# GNSS.net
KiCad netlist of a schematic drawn in Altium Designer
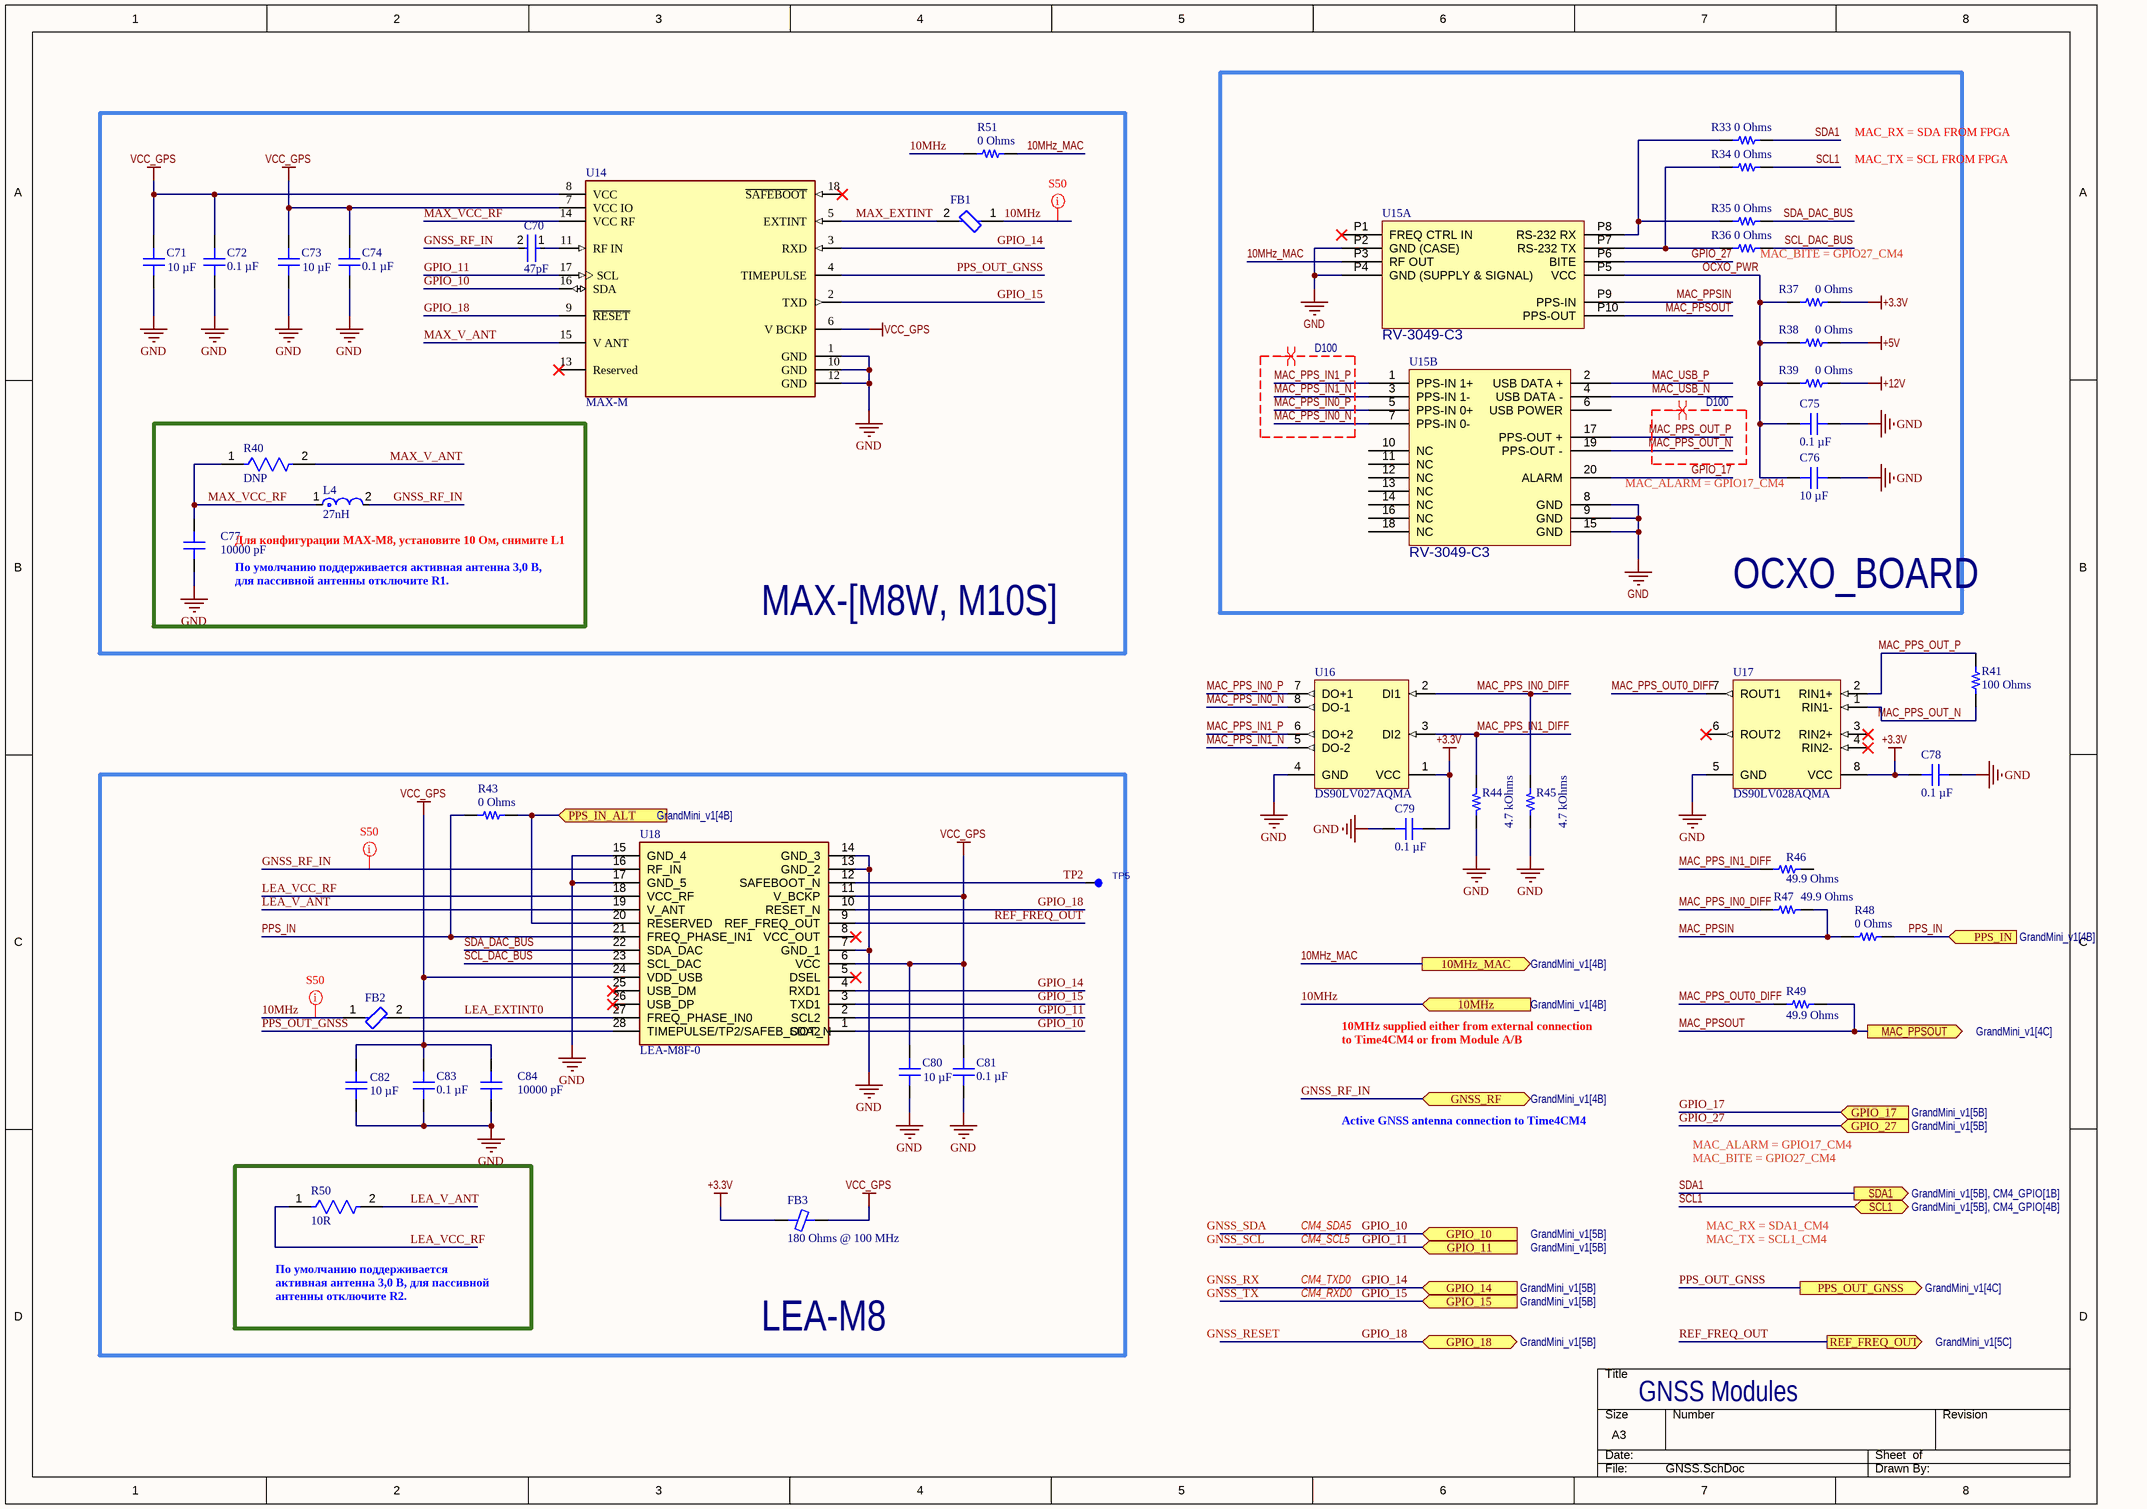
[diagram p0: GNSS.SchDoc]

(export (version "E")
  (design (tool "Eeschema 10.0.6"))
  (components
    (comp (ref "C70")
      (value "47pF")
      (footprint "FP-C0402-BB-MFG")
      (description "CAP CER 47PF 25V 5% NP0 0402")
      (fields
        (field (name "MANUFACTURER PART NUMBER") "C0402C470J3GACTU")
        (field (name "MANUFACTURER") "Kemet")
      )
      (libsource (lib "Altium Content Vault") (part "b4654b650e69147ec39a6b967a45e02"))
    )
    (comp (ref "C71")
      (value "10 µF")
      (footprint "CAP 0805_2012")
      (description "CAP CER 10UF 25V X5R 0805")
      (fields
        (field (name "TOLERANCE") "±10%")
        (field (name "CAPACITANCE") "10 µF")
        (field (name "PART NUMBER") "CC0805KKX5R8BB106")
      )
      (libsource (lib "Celestial Altium Library - altium_library") (part "Capacitor"))
    )
    (comp (ref "C72")
      (value "0.1 µF")
      (footprint "CAP 0603_1608")
      (description "CAP CER 0.1UF 50V X7R 0603")
      (fields (field (name "MANUFACTURER") "Yageo") (field (name "TOLERANCE") "±10%"))
      (libsource (lib "Celestial Altium Library - altium_library") (part "Capacitor"))
    )
    (comp (ref "C73")
      (value "~")
      (footprint "CAP 0805_2012")
      (description "CAP CER 10UF 25V X5R 0805")
      (fields
        (field (name "TOLERANCE") "±10%")
        (field (name "CAPACITANCE") "10 µF")
        (field (name "PART NUMBER") "CC0805KKX5R8BB106")
      )
      (libsource (lib "Celestial Altium Library - altium_library") (part "Capacitor"))
    )
    (comp (ref "C74")
      (value "0.1 µF")
      (footprint "CAP 0603_1608")
      (description "CAP CER 0.1UF 50V X7R 0603")
      (fields (field (name "MANUFACTURER") "Yageo") (field (name "TOLERANCE") "±10%"))
      (libsource (lib "Celestial Altium Library - altium_library") (part "Capacitor"))
    )
    (comp (ref "C75")
      (value "0.1 µF")
      (footprint "CAP 0603_1608")
      (description "CAP CER 0.1UF 50V X7R 0603")
      (fields (field (name "MANUFACTURER") "Yageo") (field (name "PART NUMBER") "CC0603KRX7R9BB104"))
      (libsource (lib "Celestial Altium Library - altium_library") (part "Capacitor"))
    )
    (comp (ref "C76")
      (value "10 µF")
      (footprint "CAP 0805_2012")
      (description "CAP CER 10UF 25V X5R 0805")
      (fields
        (field (name "TOLERANCE") "±10%")
        (field (name "CAPACITANCE") "10 µF")
        (field (name "PART NUMBER") "CC0805KKX5R8BB106")
      )
      (libsource (lib "Celestial Altium Library - altium_library") (part "Capacitor"))
    )
    (comp (ref "C77")
      (value "10000 pF")
      (footprint "CAP 0603_1608")
      (description "CAP CER 10000PF 50V X7R 0603")
      (fields (field (name "MANUFACTURER") "Yageo") (field (name "PART NUMBER") "CC0603KRX7R9BB103"))
      (libsource (lib "Celestial Altium Library - altium_library") (part "Capacitor"))
    )
    (comp (ref "C78")
      (value "0.1 µF")
      (footprint "CAP 0603_1608")
      (description "CAP CER 0.1UF 50V X7R 0603")
      (fields (field (name "MANUFACTURER") "Yageo") (field (name "PART NUMBER") "CC0603KRX7R9BB104"))
      (libsource (lib "Celestial Altium Library - altium_library") (part "Capacitor"))
    )
    (comp (ref "C79")
      (value "0.1 µF")
      (footprint "CAP 0603_1608")
      (description "CAP CER 0.1UF 50V X7R 0603")
      (fields (field (name "MANUFACTURER") "Yageo") (field (name "PART NUMBER") "CC0603KRX7R9BB104"))
      (libsource (lib "Celestial Altium Library - altium_library") (part "Capacitor"))
    )
    (comp (ref "C80")
      (value "10 µF")
      (footprint "CAP 0805_2012")
      (description "CAP CER 10UF 25V X5R 0805")
      (fields
        (field (name "TOLERANCE") "±10%")
        (field (name "CAPACITANCE") "10 µF")
        (field (name "PART NUMBER") "CC0805KKX5R8BB106")
      )
      (libsource (lib "Celestial Altium Library - altium_library") (part "Capacitor"))
    )
    (comp (ref "C81")
      (value "0.1 µF")
      (footprint "CAP 0603_1608")
      (description "CAP CER 0.1UF 50V X7R 0603")
      (fields (field (name "MANUFACTURER") "Yageo") (field (name "TOLERANCE") "±10%"))
      (libsource (lib "Celestial Altium Library - altium_library") (part "Capacitor"))
    )
    (comp (ref "C82")
      (value "10 µF")
      (footprint "CAP 0805_2012")
      (description "CAP CER 10UF 25V X5R 0805")
      (fields
        (field (name "TOLERANCE") "±10%")
        (field (name "CAPACITANCE") "10 µF")
        (field (name "PART NUMBER") "CC0805KKX5R8BB106")
      )
      (libsource (lib "Celestial Altium Library - altium_library") (part "Capacitor"))
    )
    (comp (ref "C83")
      (value "0.1 µF")
      (footprint "CAP 0603_1608")
      (description "CAP CER 0.1UF 50V X7R 0603")
      (fields (field (name "MANUFACTURER") "Yageo") (field (name "TOLERANCE") "±10%"))
      (libsource (lib "Celestial Altium Library - altium_library") (part "Capacitor"))
    )
    (comp (ref "C84")
      (value "10000 pF")
      (footprint "CAP 0603_1608")
      (description "CAP CER 10000PF 50V X7R 0603")
      (fields (field (name "MANUFACTURER") "Yageo") (field (name "PART NUMBER") "CC0603KRX7R9BB103"))
      (libsource (lib "Celestial Altium Library - altium_library") (part "Capacitor"))
    )
    (comp (ref "FB1")
      (value "BLM18HG102SH1D")
      (footprint "FP-BLM18-0_15-t0_8-IPC_C")
      (description "Chip Ferrite Bead, 0603, 1000Ω @ 100MHz, 1.6Ω, 25%, 100mA")
      (fields (field (name "TOLERANCE") "25%"))
      (libsource (lib "Altium Content Vault") (part "5f30dd21d616792df468990f7003faa"))
    )
    (comp (ref "FB2")
      (value "BLM18HG102SH1D")
      (footprint "FP-BLM18-0_15-t0_8-IPC_C")
      (description "Chip Ferrite Bead, 0603, 1000Ω @ 100MHz, 1.6Ω, 25%, 100mA")
      (fields (field (name "TOLERANCE") "25%"))
      (libsource (lib "Altium Content Vault") (part "5f30dd21d616792df468990f7003faa"))
    )
    (comp (ref "FB3")
      (value "180 Ohms @ 100 MHz")
      (footprint "FER 0603_1608")
      (description "FERRITE BEAD 180 OHM 0603 1LN")
      (fields
        (field (name "PART NUMBER") "BLM18PG181SN1D")
        (field (name "MANUFACTURER") "Murata Electronics")
      )
      (libsource (lib "Celestial Altium Library - altium_library") (part "Ferrite Chip"))
    )
    (comp (ref "L4")
      (value "27nH")
      (footprint "FP-LQG15HH_02-IPC_C")
      (description "Multilayer type RF Inductor 27nH ±5% 0.46Ω 350mA 0402")
      (fields (field (name "TOLERANCE") "5%"))
      (libsource (lib "Altium Content Vault") (part "4cc4b267dca4c8e51f7102f422741d8"))
    )
    (comp (ref "R33")
      (value "0 Ohms")
      (footprint "YAGEO RES 0805_2012")
      (description "RES 0 OHM JUMPER 1/8W 0805")
      (fields (field (name "PART NUMBER") "RC0805FR-070RL") (field (name "MANUFACTURER") "Yageo"))
      (libsource (lib "Celestial Altium Library - altium_library") (part "Resistor"))
    )
    (comp (ref "R34")
      (value "0 Ohms")
      (footprint "YAGEO RES 0805_2012")
      (description "RES 0 OHM JUMPER 1/8W 0805")
      (fields (field (name "PART NUMBER") "RC0805FR-070RL") (field (name "MANUFACTURER") "Yageo"))
      (libsource (lib "Celestial Altium Library - altium_library") (part "Resistor"))
    )
    (comp (ref "R35")
      (value "0 Ohms")
      (footprint "YAGEO RES 0805_2012")
      (description "RES 0 OHM JUMPER 1/8W 0805")
      (fields (field (name "PART NUMBER") "RC0805FR-070RL") (field (name "MANUFACTURER") "Yageo"))
      (libsource (lib "Celestial Altium Library - altium_library") (part "Resistor"))
    )
    (comp (ref "R36")
      (value "0 Ohms")
      (footprint "YAGEO RES 0805_2012")
      (description "RES 0 OHM JUMPER 1/8W 0805")
      (fields (field (name "PART NUMBER") "RC0805FR-070RL") (field (name "MANUFACTURER") "Yageo"))
      (libsource (lib "Celestial Altium Library - altium_library") (part "Resistor"))
    )
    (comp (ref "R37")
      (value "0 Ohms")
      (footprint "YAGEO RES 0805_2012")
      (description "RES 0 OHM JUMPER 1/8W 0805")
      (fields (field (name "PART NUMBER") "RC0805FR-070RL") (field (name "MANUFACTURER") "Yageo"))
      (libsource (lib "Celestial Altium Library - altium_library") (part "Resistor"))
    )
    (comp (ref "R38")
      (value "0 Ohms")
      (footprint "YAGEO RES 0805_2012")
      (description "RES 0 OHM JUMPER 1/8W 0805")
      (fields (field (name "PART NUMBER") "RC0805FR-070RL") (field (name "MANUFACTURER") "Yageo"))
      (libsource (lib "Celestial Altium Library - altium_library") (part "Resistor"))
    )
    (comp (ref "R39")
      (value "0 Ohms")
      (footprint "YAGEO RES 0805_2012")
      (description "RES 0 OHM JUMPER 1/8W 0805")
      (fields (field (name "PART NUMBER") "RC0805FR-070RL") (field (name "MANUFACTURER") "Yageo"))
      (libsource (lib "Celestial Altium Library - altium_library") (part "Resistor"))
    )
    (comp (ref "R40")
      (value "DNP")
      (footprint "FP-ERJ3EK-MFG")
      (description "RES SMD 10 OHM 1% 1/10W 0603")
      (fields
        (field (name "OCTOPART") "https://octopart.com/erj-3ekf10r0v-panasonic-55403649")
        (field (name "MANUFACTURER PART NUMBER") "ERJ-3EKF10R0V")
      )
      (libsource (lib "Altium Content Vault") (part "1029c3af85768c4190bb7ad29bc67b5"))
    )
    (comp (ref "R41")
      (value "100 Ohms")
      (footprint "YAGEO RES 0603_1608")
      (description "RES 100 OHM 1% 1/10W 0603")
      (fields (field (name "PART NUMBER") "RC0603FR-07100RL") (field (name "MANUFACTURER") "Yageo"))
      (libsource (lib "Celestial Altium Library - altium_library") (part "Resistor"))
    )
    (comp (ref "R43")
      (value "0 Ohms")
      (footprint "YAGEO RES 0805_2012")
      (description "RES 0 OHM JUMPER 1/8W 0805")
      (fields (field (name "TOLERANCE") "Jumper") (field (name "MANUFACTURER") "Yageo"))
      (libsource (lib "Celestial Altium Library - altium_library") (part "Resistor"))
    )
    (comp (ref "R44")
      (value "4.7 kOhms")
      (footprint "YAGEO RES 0402_1005")
      (description "RES 4.7K OHM 1% 1/16W 0402")
      (fields (field (name "MANUFACTURER") "Yageo") (field (name "TOLERANCE") "±1%"))
      (libsource (lib "Celestial Altium Library - altium_library") (part "Resistor"))
    )
    (comp (ref "R45")
      (value "4.7 kOhms")
      (footprint "YAGEO RES 0402_1005")
      (description "RES 4.7K OHM 1% 1/16W 0402")
      (fields (field (name "MANUFACTURER") "Yageo") (field (name "TOLERANCE") "±1%"))
      (libsource (lib "Celestial Altium Library - altium_library") (part "Resistor"))
    )
    (comp (ref "R46")
      (value "49.9 Ohms")
      (footprint "YAGEO RES 0603_1608")
      (description "RES 49.9 OHM 1% 1/10W 0603")
      (fields (field (name "PART NUMBER") "RC0603FR-0749R9L") (field (name "MANUFACTURER") "Yageo"))
      (libsource (lib "Celestial Altium Library - altium_library") (part "Resistor"))
    )
    (comp (ref "R47")
      (value "49.9 Ohms")
      (footprint "YAGEO RES 0603_1608")
      (description "RES 49.9 OHM 1% 1/10W 0603")
      (fields (field (name "PART NUMBER") "RC0603FR-0749R9L") (field (name "MANUFACTURER") "Yageo"))
      (libsource (lib "Celestial Altium Library - altium_library") (part "Resistor"))
    )
    (comp (ref "R48")
      (value "0 Ohms")
      (footprint "YAGEO RES 0805_2012")
      (description "RES 0 OHM JUMPER 1/8W 0805")
      (fields (field (name "TOLERANCE") "Jumper") (field (name "MANUFACTURER") "Yageo"))
      (libsource (lib "Celestial Altium Library - altium_library") (part "Resistor"))
    )
    (comp (ref "R49")
      (value "49.9 Ohms")
      (footprint "YAGEO RES 0603_1608")
      (description "RES 49.9 OHM 1% 1/10W 0603")
      (fields (field (name "PART NUMBER") "RC0603FR-0749R9L") (field (name "MANUFACTURER") "Yageo"))
      (libsource (lib "Celestial Altium Library - altium_library") (part "Resistor"))
    )
    (comp (ref "R50")
      (value "10R")
      (footprint "FP-ERJ3EK-MFG")
      (description "RES SMD 10 OHM 1% 1/10W 0603")
      (fields
        (field (name "OCTOPART") "https://octopart.com/erj-3ekf10r0v-panasonic-55403649")
        (field (name "MANUFACTURER PART NUMBER") "ERJ-3EKF10R0V")
      )
      (libsource (lib "Altium Content Vault") (part "1029c3af85768c4190bb7ad29bc67b5"))
    )
    (comp (ref "R51")
      (value "0 Ohms")
      (footprint "YAGEO RES 0805_2012")
      (description "RES 0 OHM JUMPER 1/8W 0805")
      (fields (field (name "TOLERANCE") "Jumper") (field (name "MANUFACTURER") "Yageo"))
      (libsource (lib "Celestial Altium Library - altium_library") (part "Resistor"))
    )
    (comp (ref "TP5")
      (value "PAD_TEST")
      (footprint "Samacsys:PAD_TEST")
      (description "Test Point")
      (fields (field (name "TOLERANCE") "{Tolerance}") (field (name "MANUFACTURER") "{Manufacturer}"))
      (libsource (lib "SamacSys") (part "PAD_TEST"))
    )
    (comp (ref "U14")
      (value "MAX-M")
      (footprint "FP-MAX-M8W-0-MFG")
      (description "RF RCVR GNSS/GPS 1.575GHZ 18LCC")
      (libsource (lib "Altium Content Vault") (part "36e94f557bbf38d877319147cff7e99"))
    )
    (comp (ref "U15")
      (value "RV-3049-C3")
      (footprint "OCXO_CARD")
      (description "MOD, MAC, MAC-SA5X, ATOMIC CLOCK")
      (fields (field (name "MFG PART NUM") "MAC-SA5X") (field (name "VELENTIUM PART NUM") "<V PART NUM>"))
      (libsource (lib "SHIWA_lib") (part "MAC-SA5X"))
    )
    (comp (ref "U16")
      (value "DS90LV027AQMA")
      (footprint "M08A_N")
      (description "Automotive LVDS Dual Differential Driver, 8-pin Narrow SOIC")
      (fields (field (name "MANUFACTURER") "National Semiconductor"))
      (libsource (lib "Altium Content Vault") (part "IN-LNDRV-DS90LV027AHM"))
    )
    (comp (ref "U17")
      (value "DS90LV028AQMA")
      (footprint "M08A_L")
      (description "Automotive LVDS Dual Differential Line Receiver, 8-pin Narrow SOIC")
      (fields (field (name "MANUFACTURER") "National Semiconductor"))
      (libsource (lib "Altium Content Vault") (part "IN-LNRX-DS90LV028AHM"))
    )
    (comp (ref "U18")
      (value "LEA-M8F-0")
      (footprint "SamacSys:LEAM8F0")
      (description "Integrated Circuit")
      (fields (field (name "MOUSER PART NUMBER") "377-LEA-M8F-0"))
      (libsource (lib "SamacSys") (part "LEA-M8F-0"))
    )
  )
  (nets
    (net (code "1") (name "+3.3V") (class "Default")
      (node (ref "C78") (pin "1") (pinfunction "1_1") (pintype "passive"))
      (node (ref "C79") (pin "2") (pinfunction "2_2") (pintype "passive"))
      (node (ref "FB3") (pin "1") (pinfunction "1_1") (pintype "passive"))
      (node (ref "R37") (pin "1") (pinfunction "1_1") (pintype "passive"))
      (node (ref "U16") (pin "1") (pinfunction "VCC_1") (pintype "power_in"))
      (node (ref "U17") (pin "8") (pinfunction "VCC_8") (pintype "power_in"))
    )
    (net (code "2") (name "+5V") (class "Default")
      (node (ref "R38") (pin "1") (pinfunction "1_1") (pintype "passive"))
    )
    (net (code "3") (name "+12V") (class "Default")
      (node (ref "R39") (pin "1") (pinfunction "1_1") (pintype "passive"))
    )
    (net (code "4") (name "/10MHz") (class "Default")
      (node (ref "FB1") (pin "1") (pinfunction "1_1") (pintype "passive"))
      (node (ref "FB2") (pin "1") (pinfunction "1_1") (pintype "passive"))
      (node (ref "R51") (pin "1") (pinfunction "1_1") (pintype "passive"))
    )
    (net (code "5") (name "/10MHz_MAC") (class "Default")
      (node (ref "R51") (pin "2") (pinfunction "2_2") (pintype "passive"))
      (node (ref "U15") (pin "P3") (pinfunction "RF_OUT_P3") (pintype "passive"))
    )
    (net (code "6") (name "/GNSS_RF_IN") (class "Default")
      (node (ref "C70") (pin "2") (pinfunction "2_2") (pintype "passive"))
      (node (ref "L4") (pin "2") (pinfunction "2_2") (pintype "passive"))
      (node (ref "U18") (pin "16") (pinfunction "RF_IN_16") (pintype "passive"))
    )
    (net (code "7") (name "/GPIO_10") (class "Default")
      (node (ref "U14") (pin "16") (pinfunction "SDA_16") (pintype "bidirectional"))
      (node (ref "U18") (pin "1") (pinfunction "SDA2_1") (pintype "passive"))
    )
    (net (code "8") (name "/GPIO_11") (class "Default")
      (node (ref "U14") (pin "17") (pinfunction "SCL_17") (pintype "input"))
      (node (ref "U18") (pin "2") (pinfunction "SCL2_2") (pintype "passive"))
    )
    (net (code "9") (name "/GPIO_14") (class "Default")
      (node (ref "U14") (pin "3") (pinfunction "RXD_3") (pintype "input"))
      (node (ref "U18") (pin "4") (pinfunction "RXD1_4") (pintype "passive"))
    )
    (net (code "10") (name "/GPIO_15") (class "Default")
      (node (ref "U14") (pin "2") (pinfunction "TXD_2") (pintype "output"))
      (node (ref "U18") (pin "3") (pinfunction "TXD1_3") (pintype "passive"))
    )
    (net (code "11") (name "/GPIO_17") (class "Default")
      (node (ref "U15") (pin "20") (pinfunction "ALARM_20") (pintype "passive"))
    )
    (net (code "12") (name "/GPIO_18") (class "Default")
      (node (ref "U14") (pin "9") (pinfunction "~{RESET}_9") (pintype "passive"))
      (node (ref "U18") (pin "10") (pinfunction "RESET_N_10") (pintype "passive"))
    )
    (net (code "13") (name "/GPIO_27") (class "Default")
      (node (ref "U15") (pin "P6") (pinfunction "BITE_P6") (pintype "passive"))
    )
    (net (code "14") (name "/LEA_EXTINT0") (class "Default")
      (node (ref "FB2") (pin "2") (pinfunction "2_2") (pintype "passive"))
      (node (ref "U18") (pin "27") (pinfunction "FREQ_PHASE_IN0_27") (pintype "passive"))
    )
    (net (code "15") (name "/LEA_VCC_RF") (class "Default")
      (node (ref "R50") (pin "1") (pinfunction "1_1") (pintype "passive"))
      (node (ref "U18") (pin "18") (pinfunction "VCC_RF_18") (pintype "passive"))
    )
    (net (code "16") (name "/LEA_V_ANT") (class "Default")
      (node (ref "R50") (pin "2") (pinfunction "2_2") (pintype "passive"))
      (node (ref "U18") (pin "19") (pinfunction "V_ANT_19") (pintype "passive"))
    )
    (net (code "17") (name "/MAC_PPSIN") (class "Default")
      (node (ref "R47") (pin "2") (pinfunction "2_2") (pintype "passive"))
      (node (ref "R48") (pin "1") (pinfunction "1_1") (pintype "passive"))
      (node (ref "U15") (pin "P9") (pinfunction "PPS-IN_P9") (pintype "passive"))
    )
    (net (code "18") (name "/MAC_PPSOUT") (class "Default")
      (node (ref "R49") (pin "2") (pinfunction "2_2") (pintype "passive"))
      (node (ref "U15") (pin "P10") (pinfunction "PPS-OUT_P10") (pintype "passive"))
    )
    (net (code "19") (name "/MAC_PPS_IN0_DIFF") (class "Default")
      (node (ref "R45") (pin "2") (pinfunction "2_2") (pintype "passive"))
      (node (ref "R47") (pin "1") (pinfunction "1_1") (pintype "passive"))
      (node (ref "U16") (pin "2") (pinfunction "DI1_2") (pintype "input"))
    )
    (net (code "20") (name "/MAC_PPS_IN0_N") (class "Default")
      (node (ref "U15") (pin "7") (pinfunction "PPS-IN_0-_7") (pintype "passive"))
      (node (ref "U16") (pin "8") (pinfunction "DO-1_8") (pintype "output"))
    )
    (net (code "21") (name "/MAC_PPS_IN0_P") (class "Default")
      (node (ref "U15") (pin "5") (pinfunction "PPS-IN_0+_5") (pintype "passive"))
      (node (ref "U16") (pin "7") (pinfunction "DO+1_7") (pintype "output"))
    )
    (net (code "22") (name "/MAC_PPS_IN1_DIFF") (class "Default")
      (node (ref "R44") (pin "2") (pinfunction "2_2") (pintype "passive"))
      (node (ref "R46") (pin "1") (pinfunction "1_1") (pintype "passive"))
      (node (ref "U16") (pin "3") (pinfunction "DI2_3") (pintype "input"))
    )
    (net (code "23") (name "/MAC_PPS_IN1_N") (class "Default")
      (node (ref "U15") (pin "3") (pinfunction "PPS-IN_1-_3") (pintype "passive"))
      (node (ref "U16") (pin "5") (pinfunction "DO-2_5") (pintype "output"))
    )
    (net (code "24") (name "/MAC_PPS_IN1_P") (class "Default")
      (node (ref "U15") (pin "1") (pinfunction "PPS-IN_1+_1") (pintype "passive"))
      (node (ref "U16") (pin "6") (pinfunction "DO+2_6") (pintype "output"))
    )
    (net (code "25") (name "/MAC_PPS_OUT0_DIFF") (class "Default")
      (node (ref "R49") (pin "1") (pinfunction "1_1") (pintype "passive"))
      (node (ref "U17") (pin "7") (pinfunction "ROUT1_7") (pintype "output"))
    )
    (net (code "26") (name "/MAC_PPS_OUT_N") (class "Default")
      (node (ref "R41") (pin "1") (pinfunction "1_1") (pintype "passive"))
      (node (ref "U15") (pin "19") (pinfunction "PPS-OUT_-_19") (pintype "passive"))
      (node (ref "U17") (pin "1") (pinfunction "RIN1-_1") (pintype "input"))
    )
    (net (code "27") (name "/MAC_PPS_OUT_P") (class "Default")
      (node (ref "R41") (pin "2") (pinfunction "2_2") (pintype "passive"))
      (node (ref "U15") (pin "17") (pinfunction "PPS-OUT_+_17") (pintype "passive"))
      (node (ref "U17") (pin "2") (pinfunction "RIN1+_2") (pintype "input"))
    )
    (net (code "28") (name "/MAC_USB_N") (class "Default")
      (node (ref "U15") (pin "4") (pinfunction "USB_DATA_-_4") (pintype "passive"))
    )
    (net (code "29") (name "/MAC_USB_P") (class "Default")
      (node (ref "U15") (pin "2") (pinfunction "USB_DATA_+_2") (pintype "passive"))
    )
    (net (code "30") (name "/MAX_EXTINT") (class "Default")
      (node (ref "FB1") (pin "2") (pinfunction "2_2") (pintype "passive"))
      (node (ref "U14") (pin "5") (pinfunction "EXTINT_5") (pintype "input"))
    )
    (net (code "31") (name "/MAX_VCC_RF") (class "Default")
      (node (ref "C77") (pin "2") (pinfunction "2_2") (pintype "passive"))
      (node (ref "L4") (pin "1") (pinfunction "1_1") (pintype "passive"))
      (node (ref "R40") (pin "1") (pinfunction "1_1") (pintype "passive"))
      (node (ref "U14") (pin "14") (pinfunction "VCC_RF_14") (pintype "power_in"))
    )
    (net (code "32") (name "/MAX_V_ANT") (class "Default")
      (node (ref "R40") (pin "2") (pinfunction "2_2") (pintype "passive"))
      (node (ref "U14") (pin "15") (pinfunction "V_ANT_15") (pintype "power_in"))
    )
    (net (code "33") (name "/OCXO_PWR") (class "Default")
      (node (ref "C75") (pin "1") (pinfunction "1_1") (pintype "passive"))
      (node (ref "C76") (pin "2") (pinfunction "2_2") (pintype "passive"))
      (node (ref "R37") (pin "2") (pinfunction "2_2") (pintype "passive"))
      (node (ref "R38") (pin "2") (pinfunction "2_2") (pintype "passive"))
      (node (ref "R39") (pin "2") (pinfunction "2_2") (pintype "passive"))
      (node (ref "U15") (pin "P5") (pinfunction "VCC_P5") (pintype "passive"))
    )
    (net (code "34") (name "/PPS_IN") (class "Default")
      (node (ref "R43") (pin "1") (pinfunction "1_1") (pintype "passive"))
      (node (ref "R48") (pin "2") (pinfunction "2_2") (pintype "passive"))
      (node (ref "U18") (pin "21") (pinfunction "FREQ_PHASE_IN1_21") (pintype "passive"))
    )
    (net (code "35") (name "/PPS_IN_ALT") (class "Default")
      (node (ref "R43") (pin "2") (pinfunction "2_2") (pintype "passive"))
      (node (ref "U18") (pin "20") (pinfunction "RESERVED_20") (pintype "passive"))
    )
    (net (code "36") (name "/PPS_OUT_GNSS") (class "Default")
      (node (ref "U14") (pin "4") (pinfunction "TIMEPULSE_4") (pintype "passive"))
      (node (ref "U18") (pin "28") (pinfunction "TIMEPULSE/TP2/SAFEB_OOT_N_28") (pintype "passive"))
    )
    (net (code "37") (name "/REF_FREQ_OUT") (class "Default")
      (node (ref "U18") (pin "9") (pinfunction "REF_FREQ_OUT_9") (pintype "passive"))
    )
    (net (code "38") (name "/SCL1") (class "Default")
      (node (ref "R34") (pin "1") (pinfunction "1_1") (pintype "passive"))
    )
    (net (code "39") (name "/SCL_DAC_BUS") (class "Default")
      (node (ref "R36") (pin "1") (pinfunction "1_1") (pintype "passive"))
      (node (ref "U18") (pin "23") (pinfunction "SCL_DAC_23") (pintype "passive"))
    )
    (net (code "40") (name "/SDA1") (class "Default")
      (node (ref "R33") (pin "1") (pinfunction "1_1") (pintype "passive"))
    )
    (net (code "41") (name "/SDA_DAC_BUS") (class "Default")
      (node (ref "R35") (pin "1") (pinfunction "1_1") (pintype "passive"))
      (node (ref "U18") (pin "22") (pinfunction "SDA_DAC_22") (pintype "passive"))
    )
    (net (code "42") (name "/TP2") (class "Default")
      (node (ref "TP5") (pin "1") (pinfunction "1_1") (pintype "passive"))
      (node (ref "U18") (pin "12") (pinfunction "SAFEBOOT_N_12") (pintype "passive"))
    )
    (net (code "43") (name "GND") (class "Default")
      (node (ref "C71") (pin "1") (pinfunction "1_1") (pintype "passive"))
      (node (ref "C72") (pin "1") (pinfunction "1_1") (pintype "passive"))
      (node (ref "C73") (pin "1") (pinfunction "1_1") (pintype "passive"))
      (node (ref "C74") (pin "1") (pinfunction "1_1") (pintype "passive"))
      (node (ref "C75") (pin "2") (pinfunction "2_2") (pintype "passive"))
      (node (ref "C76") (pin "1") (pinfunction "1_1") (pintype "passive"))
      (node (ref "C77") (pin "1") (pinfunction "1_1") (pintype "passive"))
      (node (ref "C78") (pin "2") (pinfunction "2_2") (pintype "passive"))
      (node (ref "C79") (pin "1") (pinfunction "1_1") (pintype "passive"))
      (node (ref "C80") (pin "1") (pinfunction "1_1") (pintype "passive"))
      (node (ref "C81") (pin "1") (pinfunction "1_1") (pintype "passive"))
      (node (ref "C82") (pin "1") (pinfunction "1_1") (pintype "passive"))
      (node (ref "C83") (pin "1") (pinfunction "1_1") (pintype "passive"))
      (node (ref "C84") (pin "1") (pinfunction "1_1") (pintype "passive"))
      (node (ref "R44") (pin "1") (pinfunction "1_1") (pintype "passive"))
      (node (ref "R45") (pin "1") (pinfunction "1_1") (pintype "passive"))
      (node (ref "U14") (pin "1") (pinfunction "GND_1") (pintype "power_in"))
      (node (ref "U14") (pin "10") (pinfunction "GND_10") (pintype "power_in"))
      (node (ref "U14") (pin "12") (pinfunction "GND_12") (pintype "power_in"))
      (node (ref "U15") (pin "15") (pinfunction "GND_15") (pintype "passive"))
      (node (ref "U15") (pin "8") (pinfunction "GND_8") (pintype "passive"))
      (node (ref "U15") (pin "9") (pinfunction "GND_9") (pintype "passive"))
      (node (ref "U15") (pin "P2") (pinfunction "GND_(CASE)_P2") (pintype "passive"))
      (node (ref "U15") (pin "P4") (pinfunction "GND_(SUPPLY_&_SIGNAL)_P4") (pintype "passive"))
      (node (ref "U16") (pin "4") (pinfunction "GND_4") (pintype "power_in"))
      (node (ref "U17") (pin "5") (pinfunction "GND_5") (pintype "power_in"))
      (node (ref "U18") (pin "13") (pinfunction "GND_2_13") (pintype "passive"))
      (node (ref "U18") (pin "14") (pinfunction "GND_3_14") (pintype "passive"))
      (node (ref "U18") (pin "15") (pinfunction "GND_4_15") (pintype "passive"))
      (node (ref "U18") (pin "17") (pinfunction "GND_5_17") (pintype "passive"))
      (node (ref "U18") (pin "7") (pinfunction "GND_1_7") (pintype "passive"))
    )
    (net (code "44") (name "Net-(U14-RF_IN)") (class "Default")
      (node (ref "C70") (pin "1") (pinfunction "1_1") (pintype "passive"))
      (node (ref "U14") (pin "11") (pinfunction "RF_IN_11") (pintype "input"))
    )
    (net (code "45") (name "Net-(U15A-RS-232_RX)") (class "Default")
      (node (ref "R33") (pin "2") (pinfunction "2_2") (pintype "passive"))
      (node (ref "R35") (pin "2") (pinfunction "2_2") (pintype "passive"))
      (node (ref "U15") (pin "P8") (pinfunction "RS-232_RX_P8") (pintype "passive"))
    )
    (net (code "46") (name "Net-(U15A-RS-232_TX)") (class "Default")
      (node (ref "R34") (pin "2") (pinfunction "2_2") (pintype "passive"))
      (node (ref "R36") (pin "2") (pinfunction "2_2") (pintype "passive"))
      (node (ref "U15") (pin "P7") (pinfunction "RS-232_TX_P7") (pintype "passive"))
    )
    (net (code "47") (name "VCC_GPS") (class "Default")
      (node (ref "C71") (pin "2") (pinfunction "2_2") (pintype "passive"))
      (node (ref "C72") (pin "2") (pinfunction "2_2") (pintype "passive"))
      (node (ref "C73") (pin "2") (pinfunction "2_2") (pintype "passive"))
      (node (ref "C74") (pin "2") (pinfunction "2_2") (pintype "passive"))
      (node (ref "C80") (pin "2") (pinfunction "2_2") (pintype "passive"))
      (node (ref "C81") (pin "2") (pinfunction "2_2") (pintype "passive"))
      (node (ref "C82") (pin "2") (pinfunction "2_2") (pintype "passive"))
      (node (ref "C83") (pin "2") (pinfunction "2_2") (pintype "passive"))
      (node (ref "C84") (pin "2") (pinfunction "2_2") (pintype "passive"))
      (node (ref "FB3") (pin "2") (pinfunction "2_2") (pintype "passive"))
      (node (ref "U14") (pin "6") (pinfunction "V_BCKP_6") (pintype "power_in"))
      (node (ref "U14") (pin "7") (pinfunction "VCC_IO_7") (pintype "power_in"))
      (node (ref "U14") (pin "8") (pinfunction "VCC_8") (pintype "power_in"))
      (node (ref "U18") (pin "11") (pinfunction "V_BCKP_11") (pintype "passive"))
      (node (ref "U18") (pin "24") (pinfunction "VDD_USB_24") (pintype "passive"))
      (node (ref "U18") (pin "6") (pinfunction "VCC_6") (pintype "passive"))
    )
    (net (code "48") (name "unconnected-(R46-Pad2)") (class "Default")
      (node (ref "R46") (pin "2") (pinfunction "2_2") (pintype "passive"))
    )
    (net (code "49") (name "unconnected-(U14-Reserved-Pad13)") (class "Default")
      (node (ref "U14") (pin "13") (pinfunction "Reserved_13") (pintype "passive+no_connect"))
    )
    (net (code "50") (name "unconnected-(U14-~{SAFEBOOT}-Pad18)") (class "Default")
      (node (ref "U14") (pin "18") (pinfunction "~{SAFEBOOT}_18") (pintype "input+no_connect"))
    )
    (net (code "51") (name "unconnected-(U15A-FREQ_CTRL_IN-PadP1)") (class "Default")
      (node (ref "U15") (pin "P1") (pinfunction "FREQ_CTRL_IN_P1") (pintype "passive+no_connect"))
    )
    (net (code "52") (name "unconnected-(U15B-NC-Pad10)") (class "Default")
      (node (ref "U15") (pin "10") (pinfunction "NC_10") (pintype "passive"))
    )
    (net (code "53") (name "unconnected-(U15B-NC-Pad11)") (class "Default")
      (node (ref "U15") (pin "11") (pinfunction "NC_11") (pintype "passive"))
    )
    (net (code "54") (name "unconnected-(U15B-NC-Pad12)") (class "Default")
      (node (ref "U15") (pin "12") (pinfunction "NC_12") (pintype "passive"))
    )
    (net (code "55") (name "unconnected-(U15B-NC-Pad13)") (class "Default")
      (node (ref "U15") (pin "13") (pinfunction "NC_13") (pintype "passive"))
    )
    (net (code "56") (name "unconnected-(U15B-NC-Pad14)") (class "Default")
      (node (ref "U15") (pin "14") (pinfunction "NC_14") (pintype "passive"))
    )
    (net (code "57") (name "unconnected-(U15B-NC-Pad16)") (class "Default")
      (node (ref "U15") (pin "16") (pinfunction "NC_16") (pintype "passive"))
    )
    (net (code "58") (name "unconnected-(U15B-NC-Pad18)") (class "Default")
      (node (ref "U15") (pin "18") (pinfunction "NC_18") (pintype "passive"))
    )
    (net (code "59") (name "unconnected-(U15B-USB_POWER-Pad6)") (class "Default")
      (node (ref "U15") (pin "6") (pinfunction "USB_POWER_6") (pintype "passive"))
    )
    (net (code "60") (name "unconnected-(U17-RIN2+-Pad3)") (class "Default")
      (node (ref "U17") (pin "3") (pinfunction "RIN2+_3") (pintype "input+no_connect"))
    )
    (net (code "61") (name "unconnected-(U17-RIN2--Pad4)") (class "Default")
      (node (ref "U17") (pin "4") (pinfunction "RIN2-_4") (pintype "input+no_connect"))
    )
    (net (code "62") (name "unconnected-(U17-ROUT2-Pad6)") (class "Default")
      (node (ref "U17") (pin "6") (pinfunction "ROUT2_6") (pintype "output+no_connect"))
    )
    (net (code "63") (name "unconnected-(U18-DSEL-Pad5)") (class "Default")
      (node (ref "U18") (pin "5") (pinfunction "DSEL_5") (pintype "passive+no_connect"))
    )
    (net (code "64") (name "unconnected-(U18-USB_DM-Pad25)") (class "Default")
      (node (ref "U18") (pin "25") (pinfunction "USB_DM_25") (pintype "passive+no_connect"))
    )
    (net (code "65") (name "unconnected-(U18-USB_DP-Pad26)") (class "Default")
      (node (ref "U18") (pin "26") (pinfunction "USB_DP_26") (pintype "passive+no_connect"))
    )
    (net (code "66") (name "unconnected-(U18-VCC_OUT-Pad8)") (class "Default")
      (node (ref "U18") (pin "8") (pinfunction "VCC_OUT_8") (pintype "passive+no_connect"))
    )
  )
)
